# gps_tracker_A2235h.net
KiCad netlist of a schematic drawn in EAGLE
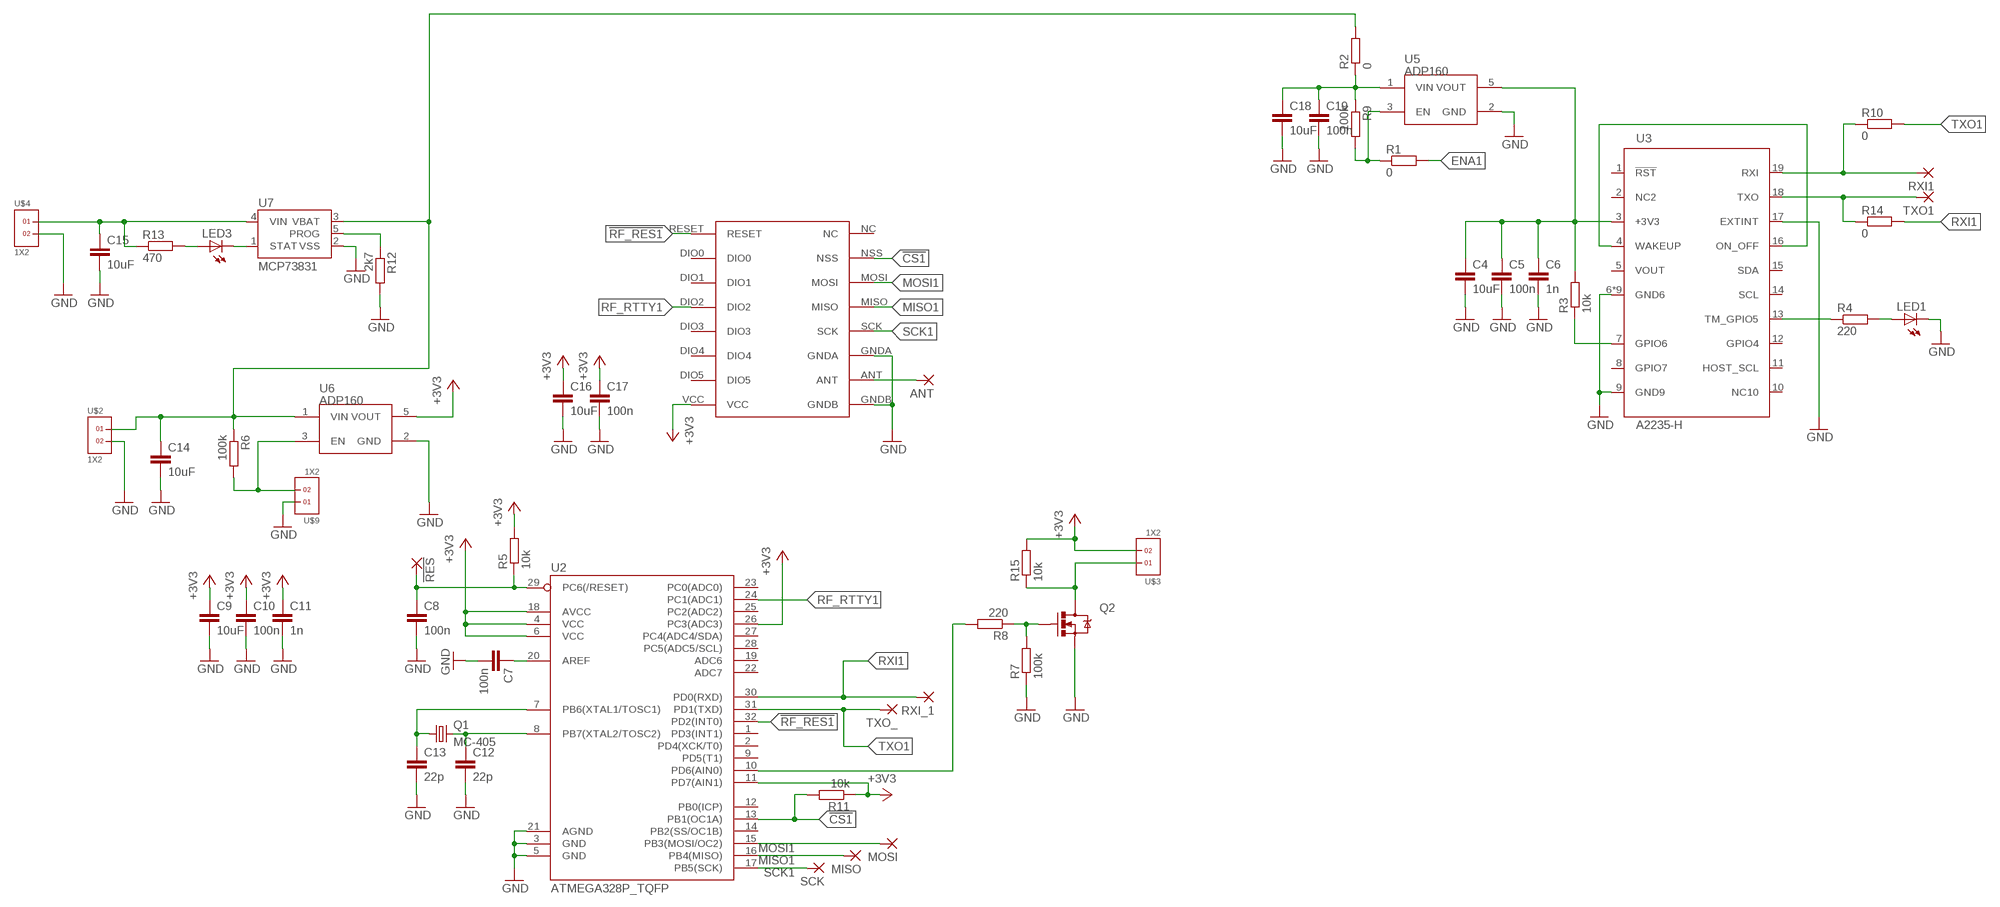
[diagram p0: schematic, sheet 1]

(export (version "E")
  (design (tool "Eeschema 10.0.6"))
  (components
    (comp (ref "!RES")
      (value "SMD2")
      (footprint "eagle-import:SMD1,27-2,54")
      (libsource (lib "eagle-import") (part "SMD2"))
    )
    (comp (ref "ANT")
      (value "SMD2")
      (footprint "eagle-import:SMD1,27-2,54")
      (libsource (lib "eagle-import") (part "SMD2"))
    )
    (comp (ref "C4")
      (value "10uF")
      (footprint "eagle-import:C0603")
      (libsource (lib "eagle-import") (part "C-EUC0603"))
    )
    (comp (ref "C5")
      (value "100n")
      (footprint "eagle-import:C0603")
      (libsource (lib "eagle-import") (part "C-EUC0603"))
    )
    (comp (ref "C6")
      (value "1n")
      (footprint "eagle-import:C0603")
      (libsource (lib "eagle-import") (part "C-EUC0603"))
    )
    (comp (ref "C7")
      (value "100n")
      (footprint "eagle-import:C0603")
      (libsource (lib "eagle-import") (part "C-EUC0603"))
    )
    (comp (ref "C8")
      (value "100n")
      (footprint "eagle-import:C0603")
      (libsource (lib "eagle-import") (part "C-EUC0603"))
    )
    (comp (ref "C9")
      (value "10uF")
      (footprint "eagle-import:C0603")
      (libsource (lib "eagle-import") (part "C-EUC0603"))
    )
    (comp (ref "C10")
      (value "100n")
      (footprint "eagle-import:C0603")
      (libsource (lib "eagle-import") (part "C-EUC0603"))
    )
    (comp (ref "C11")
      (value "1n")
      (footprint "eagle-import:C0603")
      (libsource (lib "eagle-import") (part "C-EUC0603"))
    )
    (comp (ref "C12")
      (value "22p")
      (footprint "eagle-import:C0603")
      (libsource (lib "eagle-import") (part "C-EUC0603"))
    )
    (comp (ref "C13")
      (value "22p")
      (footprint "eagle-import:C0603")
      (libsource (lib "eagle-import") (part "C-EUC0603"))
    )
    (comp (ref "C14")
      (value "10uF")
      (footprint "eagle-import:C0603")
      (libsource (lib "eagle-import") (part "C-EUC0603"))
    )
    (comp (ref "C15")
      (value "10uF")
      (footprint "eagle-import:C0603")
      (libsource (lib "eagle-import") (part "C-EUC0603"))
    )
    (comp (ref "C16")
      (value "10uF")
      (footprint "eagle-import:C0603")
      (libsource (lib "eagle-import") (part "C-EUC0603"))
    )
    (comp (ref "C17")
      (value "100n")
      (footprint "eagle-import:C0603")
      (libsource (lib "eagle-import") (part "C-EUC0603"))
    )
    (comp (ref "C18")
      (value "10uF")
      (footprint "eagle-import:C0603")
      (libsource (lib "eagle-import") (part "C-EUC0603"))
    )
    (comp (ref "C19")
      (value "100n")
      (footprint "eagle-import:C0603")
      (libsource (lib "eagle-import") (part "C-EUC0603"))
    )
    (comp (ref "LED1")
      (value "LEDCHIPLED_0603")
      (footprint "eagle-import:CHIPLED_0603")
      (libsource (lib "eagle-import") (part "LEDCHIPLED_0603"))
    )
    (comp (ref "LED3")
      (value "LEDCHIPLED_0603")
      (footprint "eagle-import:CHIPLED_0603")
      (libsource (lib "eagle-import") (part "LEDCHIPLED_0603"))
    )
    (comp (ref "MISO")
      (value "SMD2")
      (footprint "eagle-import:SMD1,27-2,54")
      (libsource (lib "eagle-import") (part "SMD2"))
    )
    (comp (ref "MOSI")
      (value "SMD2")
      (footprint "eagle-import:SMD1,27-2,54")
      (libsource (lib "eagle-import") (part "SMD2"))
    )
    (comp (ref "Q1")
      (value "MC-405")
      (footprint "eagle-import:MC-405")
      (libsource (lib "eagle-import") (part "MC-405"))
    )
    (comp (ref "Q2")
      (value "MOSFET-NCHANNELAO3404A")
      (footprint "eagle-import:SOT23-3")
      (libsource (lib "eagle-import") (part "MOSFET-NCHANNELAO3404A"))
    )
    (comp (ref "R1")
      (value "0")
      (footprint "eagle-import:R0603")
      (libsource (lib "eagle-import") (part "R-EU_R0603"))
    )
    (comp (ref "R2")
      (value "0")
      (footprint "eagle-import:R0603")
      (libsource (lib "eagle-import") (part "R-EU_R0603"))
    )
    (comp (ref "R3")
      (value "10k")
      (footprint "eagle-import:R0603")
      (libsource (lib "eagle-import") (part "R-EU_R0603"))
    )
    (comp (ref "R4")
      (value "220")
      (footprint "eagle-import:R0603")
      (libsource (lib "eagle-import") (part "R-EU_R0603"))
    )
    (comp (ref "R5")
      (value "10k")
      (footprint "eagle-import:R0603")
      (libsource (lib "eagle-import") (part "R-EU_R0603"))
    )
    (comp (ref "R6")
      (value "100k")
      (footprint "eagle-import:R0603")
      (libsource (lib "eagle-import") (part "R-EU_R0603"))
    )
    (comp (ref "R7")
      (value "100k")
      (footprint "eagle-import:R0603")
      (libsource (lib "eagle-import") (part "R-EU_R0603"))
    )
    (comp (ref "R8")
      (value "220")
      (footprint "eagle-import:R0603")
      (libsource (lib "eagle-import") (part "R-EU_R0603"))
    )
    (comp (ref "R9")
      (value "100k")
      (footprint "eagle-import:R0603")
      (libsource (lib "eagle-import") (part "R-EU_R0603"))
    )
    (comp (ref "R10")
      (value "0")
      (footprint "eagle-import:R0603")
      (libsource (lib "eagle-import") (part "R-EU_R0603"))
    )
    (comp (ref "R11")
      (value "10k")
      (footprint "eagle-import:R0603")
      (libsource (lib "eagle-import") (part "R-EU_R0603"))
    )
    (comp (ref "R12")
      (value "2k7")
      (footprint "eagle-import:R0603")
      (libsource (lib "eagle-import") (part "R-EU_R0603"))
    )
    (comp (ref "R13")
      (value "470")
      (footprint "eagle-import:R0603")
      (libsource (lib "eagle-import") (part "R-EU_R0603"))
    )
    (comp (ref "R14")
      (value "0")
      (footprint "eagle-import:R0603")
      (libsource (lib "eagle-import") (part "R-EU_R0603"))
    )
    (comp (ref "R15")
      (value "10k")
      (footprint "eagle-import:R0603")
      (libsource (lib "eagle-import") (part "R-EU_R0603"))
    )
    (comp (ref "RXI1")
      (value "SMD2")
      (footprint "eagle-import:SMD1,27-2,54")
      (libsource (lib "eagle-import") (part "SMD2"))
    )
    (comp (ref "RXI_1")
      (value "SMD2")
      (footprint "eagle-import:SMD1,27-2,54")
      (libsource (lib "eagle-import") (part "SMD2"))
    )
    (comp (ref "SCK")
      (value "SMD2")
      (footprint "eagle-import:SMD1,27-2,54")
      (libsource (lib "eagle-import") (part "SMD2"))
    )
    (comp (ref "TXO1")
      (value "SMD2")
      (footprint "eagle-import:SMD1,27-2,54")
      (libsource (lib "eagle-import") (part "SMD2"))
    )
    (comp (ref "TXO_")
      (value "SMD2")
      (footprint "eagle-import:SMD1,27-2,54")
      (libsource (lib "eagle-import") (part "SMD2"))
    )
    (comp (ref "U$2")
      (value "1X2")
      (footprint "eagle-import:1X2")
      (libsource (lib "eagle-import") (part "1X2"))
    )
    (comp (ref "U$3")
      (value "1X2")
      (footprint "eagle-import:1X2")
      (libsource (lib "eagle-import") (part "1X2"))
    )
    (comp (ref "U$4")
      (value "1X2")
      (footprint "eagle-import:1X2")
      (libsource (lib "eagle-import") (part "1X2"))
    )
    (comp (ref "U$5")
      (value "RFM69HW")
      (footprint "eagle-import:RFM")
      (libsource (lib "eagle-import") (part "RFM69HW"))
    )
    (comp (ref "U$9")
      (value "1X2")
      (footprint "eagle-import:1X2")
      (libsource (lib "eagle-import") (part "1X2"))
    )
    (comp (ref "U2")
      (value "ATMEGA328P_TQFP")
      (footprint "eagle-import:TQFP32-08")
      (libsource (lib "eagle-import") (part "ATMEGA328P_TQFP"))
    )
    (comp (ref "U3")
      (value "A2235-H")
      (footprint "eagle-import:A2235-H")
      (libsource (lib "eagle-import") (part "A2235-H"))
    )
    (comp (ref "U5")
      (value "ADP160")
      (footprint "eagle-import:SOT23-5")
      (libsource (lib "eagle-import") (part "ADP160"))
    )
    (comp (ref "U6")
      (value "ADP160")
      (footprint "eagle-import:SOT23-5")
      (libsource (lib "eagle-import") (part "ADP160"))
    )
    (comp (ref "U7")
      (value "MCP73831")
      (footprint "eagle-import:SOT23-5")
      (libsource (lib "eagle-import") (part "MCP73831"))
    )
  )
  (nets
    (net (code "1") (name "+3V3") (class "Default")
      (node (ref "C10") (pin "1") (pinfunction "1_1") (pintype "passive"))
      (node (ref "C11") (pin "1") (pinfunction "1_1") (pintype "passive"))
      (node (ref "C16") (pin "1") (pinfunction "1_1") (pintype "passive"))
      (node (ref "C17") (pin "1") (pinfunction "1_1") (pintype "passive"))
      (node (ref "C9") (pin "1") (pinfunction "1_1") (pintype "passive"))
      (node (ref "R11") (pin "1") (pinfunction "1_1") (pintype "passive"))
      (node (ref "R15") (pin "2") (pinfunction "2_2") (pintype "passive"))
      (node (ref "R5") (pin "2") (pinfunction "2_2") (pintype "passive"))
      (node (ref "U$3") (pin "2") (pinfunction "2_2") (pintype "bidirectional"))
      (node (ref "U$5") (pin "VCC") (pinfunction "VCC_VCC") (pintype "bidirectional"))
      (node (ref "U2") (pin "11") (pinfunction "PD7(AIN1)_11") (pintype "bidirectional"))
      (node (ref "U2") (pin "18") (pinfunction "AVCC_18") (pintype "bidirectional"))
      (node (ref "U2") (pin "26") (pinfunction "PC3(ADC3)_26") (pintype "bidirectional"))
      (node (ref "U2") (pin "4") (pinfunction "VCC_4") (pintype "bidirectional"))
      (node (ref "U2") (pin "6") (pinfunction "VCC_6") (pintype "bidirectional"))
      (node (ref "U6") (pin "5") (pinfunction "VOUT_5") (pintype "bidirectional"))
    )
    (net (code "2") (name "/VOUT") (class "Default")
      (node (ref "U3") (pin "5") (pinfunction "VOUT_5") (pintype "power_in"))
    )
    (net (code "3") (name "/~{CS1}") (class "Default")
      (node (ref "R11") (pin "2") (pinfunction "2_2") (pintype "passive"))
      (node (ref "U$5") (pin "NSS") (pinfunction "NSS_NSS") (pintype "bidirectional"))
      (node (ref "U2") (pin "13") (pinfunction "PB1(OC1A)_13") (pintype "bidirectional"))
    )
    (net (code "4") (name "/~{RF_RES1}") (class "Default")
      (node (ref "U$5") (pin "RESET") (pinfunction "RESET_RESET") (pintype "bidirectional"))
      (node (ref "U2") (pin "32") (pinfunction "PD2(INT0)_32") (pintype "bidirectional"))
    )
    (net (code "5") (name "ENA1") (class "Default")
      (node (ref "R1") (pin "2") (pinfunction "2_2") (pintype "passive"))
      (node (ref "R6") (pin "2") (pinfunction "2_2") (pintype "passive"))
      (node (ref "U$9") (pin "2") (pinfunction "2_2") (pintype "bidirectional"))
      (node (ref "U6") (pin "3") (pinfunction "EN_3") (pintype "bidirectional"))
    )
    (net (code "6") (name "GND") (class "Default")
      (node (ref "C10") (pin "2") (pinfunction "2_2") (pintype "passive"))
      (node (ref "C11") (pin "2") (pinfunction "2_2") (pintype "passive"))
      (node (ref "C12") (pin "2") (pinfunction "2_2") (pintype "passive"))
      (node (ref "C13") (pin "2") (pinfunction "2_2") (pintype "passive"))
      (node (ref "C14") (pin "2") (pinfunction "2_2") (pintype "passive"))
      (node (ref "C15") (pin "2") (pinfunction "2_2") (pintype "passive"))
      (node (ref "C16") (pin "2") (pinfunction "2_2") (pintype "passive"))
      (node (ref "C17") (pin "2") (pinfunction "2_2") (pintype "passive"))
      (node (ref "C18") (pin "2") (pinfunction "2_2") (pintype "passive"))
      (node (ref "C19") (pin "2") (pinfunction "2_2") (pintype "passive"))
      (node (ref "C4") (pin "2") (pinfunction "2_2") (pintype "passive"))
      (node (ref "C5") (pin "2") (pinfunction "2_2") (pintype "passive"))
      (node (ref "C6") (pin "2") (pinfunction "2_2") (pintype "passive"))
      (node (ref "C7") (pin "2") (pinfunction "2_2") (pintype "passive"))
      (node (ref "C8") (pin "2") (pinfunction "2_2") (pintype "passive"))
      (node (ref "C9") (pin "2") (pinfunction "2_2") (pintype "passive"))
      (node (ref "LED1") (pin "C") (pinfunction "C_C") (pintype "passive"))
      (node (ref "Q2") (pin "2") (pinfunction "S_2") (pintype "passive"))
      (node (ref "R12") (pin "2") (pinfunction "2_2") (pintype "passive"))
      (node (ref "R7") (pin "1") (pinfunction "1_1") (pintype "passive"))
      (node (ref "U$2") (pin "2") (pinfunction "2_2") (pintype "bidirectional"))
      (node (ref "U$4") (pin "2") (pinfunction "2_2") (pintype "bidirectional"))
      (node (ref "U$5") (pin "GNDA") (pinfunction "GNDA_GNDA") (pintype "bidirectional"))
      (node (ref "U$5") (pin "GNDB") (pinfunction "GNDB_GNDB") (pintype "bidirectional"))
      (node (ref "U$9") (pin "1") (pinfunction "1_1") (pintype "bidirectional"))
      (node (ref "U2") (pin "21") (pinfunction "AGND_21") (pintype "bidirectional"))
      (node (ref "U2") (pin "3") (pinfunction "GND_3") (pintype "bidirectional"))
      (node (ref "U2") (pin "5") (pinfunction "GND_5") (pintype "bidirectional"))
      (node (ref "U3") (pin "101") (pinfunction "GND6_101") (pintype "power_in"))
      (node (ref "U3") (pin "102") (pinfunction "GND6_102") (pintype "power_in"))
      (node (ref "U3") (pin "103") (pinfunction "GND6_103") (pintype "power_in"))
      (node (ref "U3") (pin "104") (pinfunction "GND6_104") (pintype "power_in"))
      (node (ref "U3") (pin "105") (pinfunction "GND6_105") (pintype "power_in"))
      (node (ref "U3") (pin "106") (pinfunction "GND6_106") (pintype "power_in"))
      (node (ref "U3") (pin "107") (pinfunction "GND6_107") (pintype "power_in"))
      (node (ref "U3") (pin "108") (pinfunction "GND6_108") (pintype "power_in"))
      (node (ref "U3") (pin "17") (pinfunction "EXTINT_17") (pintype "input"))
      (node (ref "U3") (pin "6") (pinfunction "GND6_6") (pintype "power_in"))
      (node (ref "U3") (pin "9") (pinfunction "GND9_9") (pintype "power_in"))
      (node (ref "U5") (pin "2") (pinfunction "GND_2") (pintype "bidirectional"))
      (node (ref "U6") (pin "2") (pinfunction "GND_2") (pintype "bidirectional"))
      (node (ref "U7") (pin "2") (pinfunction "VSS_2") (pintype "power_in"))
    )
    (net (code "7") (name "MISO1") (class "Default")
      (node (ref "MISO") (pin "1") (pinfunction "P_1") (pintype "passive"))
      (node (ref "U$5") (pin "MISO") (pinfunction "MISO_MISO") (pintype "bidirectional"))
      (node (ref "U2") (pin "16") (pinfunction "PB4(MISO)_16") (pintype "bidirectional"))
    )
    (net (code "8") (name "MOSI1") (class "Default")
      (node (ref "MOSI") (pin "1") (pinfunction "P_1") (pintype "passive"))
      (node (ref "U$5") (pin "MOSI") (pinfunction "MOSI_MOSI") (pintype "bidirectional"))
      (node (ref "U2") (pin "15") (pinfunction "PB3(MOSI/OC2)_15") (pintype "bidirectional"))
    )
    (net (code "9") (name "Net-(!RES-P)") (class "Default")
      (node (ref "!RES") (pin "1") (pinfunction "P_1") (pintype "passive"))
      (node (ref "C8") (pin "1") (pinfunction "1_1") (pintype "passive"))
      (node (ref "R5") (pin "1") (pinfunction "1_1") (pintype "passive"))
      (node (ref "U2") (pin "29") (pinfunction "PC6(/RESET)_29") (pintype "bidirectional"))
    )
    (net (code "10") (name "Net-(ANT-P)") (class "Default")
      (node (ref "ANT") (pin "1") (pinfunction "P_1") (pintype "passive"))
      (node (ref "U$5") (pin "ANT") (pinfunction "ANT_ANT") (pintype "bidirectional"))
    )
    (net (code "11") (name "Net-(LED1-PadA)") (class "Default")
      (node (ref "LED1") (pin "A") (pinfunction "A_A") (pintype "passive"))
      (node (ref "R4") (pin "2") (pinfunction "2_2") (pintype "passive"))
    )
    (net (code "12") (name "Net-(LED3-PadA)") (class "Default")
      (node (ref "LED3") (pin "A") (pinfunction "A_A") (pintype "passive"))
      (node (ref "R13") (pin "2") (pinfunction "2_2") (pintype "passive"))
    )
    (net (code "13") (name "Net-(Q2-D)") (class "Default")
      (node (ref "Q2") (pin "3") (pinfunction "D_3") (pintype "passive"))
      (node (ref "R15") (pin "1") (pinfunction "1_1") (pintype "passive"))
      (node (ref "U$3") (pin "1") (pinfunction "1_1") (pintype "bidirectional"))
    )
    (net (code "14") (name "Net-(Q2-G)") (class "Default")
      (node (ref "Q2") (pin "1") (pinfunction "G_1") (pintype "passive"))
      (node (ref "R7") (pin "2") (pinfunction "2_2") (pintype "passive"))
      (node (ref "R8") (pin "1") (pinfunction "1_1") (pintype "passive"))
    )
    (net (code "15") (name "Net-(RXI1-P)") (class "Default")
      (node (ref "R10") (pin "1") (pinfunction "1_1") (pintype "passive"))
      (node (ref "RXI1") (pin "1") (pinfunction "P_1") (pintype "passive"))
      (node (ref "U3") (pin "19") (pinfunction "RXI_19") (pintype "input"))
    )
    (net (code "16") (name "Net-(TXO1-P)") (class "Default")
      (node (ref "R14") (pin "1") (pinfunction "1_1") (pintype "passive"))
      (node (ref "TXO1") (pin "1") (pinfunction "P_1") (pintype "passive"))
      (node (ref "U3") (pin "18") (pinfunction "TXO_18") (pintype "output"))
    )
    (net (code "17") (name "Net-(U2-AREF)") (class "Default")
      (node (ref "C7") (pin "1") (pinfunction "1_1") (pintype "passive"))
      (node (ref "U2") (pin "20") (pinfunction "AREF_20") (pintype "bidirectional"))
    )
    (net (code "18") (name "Net-(U2-PB6(XTAL1{slash}TOSC1))") (class "Default")
      (node (ref "C13") (pin "1") (pinfunction "1_1") (pintype "passive"))
      (node (ref "Q1") (pin "1") (pinfunction "1_1") (pintype "passive"))
      (node (ref "U2") (pin "7") (pinfunction "PB6(XTAL1/TOSC1)_7") (pintype "bidirectional"))
    )
    (net (code "19") (name "Net-(U2-PB7(XTAL2{slash}TOSC2))") (class "Default")
      (node (ref "C12") (pin "1") (pinfunction "1_1") (pintype "passive"))
      (node (ref "Q1") (pin "2") (pinfunction "2_2") (pintype "passive"))
      (node (ref "U2") (pin "8") (pinfunction "PB7(XTAL2/TOSC2)_8") (pintype "bidirectional"))
    )
    (net (code "20") (name "Net-(U2-PD6(AIN0))") (class "Default")
      (node (ref "R8") (pin "2") (pinfunction "2_2") (pintype "passive"))
      (node (ref "U2") (pin "10") (pinfunction "PD6(AIN0)_10") (pintype "bidirectional"))
    )
    (net (code "21") (name "Net-(U3-+3V3)") (class "Default")
      (node (ref "C4") (pin "1") (pinfunction "1_1") (pintype "passive"))
      (node (ref "C5") (pin "1") (pinfunction "1_1") (pintype "passive"))
      (node (ref "C6") (pin "1") (pinfunction "1_1") (pintype "passive"))
      (node (ref "R3") (pin "2") (pinfunction "2_2") (pintype "passive"))
      (node (ref "U3") (pin "3") (pinfunction "+3V3_3") (pintype "power_in"))
      (node (ref "U5") (pin "5") (pinfunction "VOUT_5") (pintype "bidirectional"))
    )
    (net (code "22") (name "Net-(U3-GPIO6)") (class "Default")
      (node (ref "R3") (pin "1") (pinfunction "1_1") (pintype "passive"))
      (node (ref "U3") (pin "7") (pinfunction "GPIO6_7") (pintype "input"))
    )
    (net (code "23") (name "Net-(U3-ON_OFF)") (class "Default")
      (node (ref "U3") (pin "16") (pinfunction "ON_OFF_16") (pintype "input"))
      (node (ref "U3") (pin "4") (pinfunction "WAKEUP_4") (pintype "output"))
    )
    (net (code "24") (name "Net-(U3-TM_GPIO5)") (class "Default")
      (node (ref "R4") (pin "1") (pinfunction "1_1") (pintype "passive"))
      (node (ref "U3") (pin "13") (pinfunction "TM_GPIO5_13") (pintype "output"))
    )
    (net (code "25") (name "Net-(U5-EN)") (class "Default")
      (node (ref "R1") (pin "1") (pinfunction "1_1") (pintype "passive"))
      (node (ref "R9") (pin "2") (pinfunction "2_2") (pintype "passive"))
      (node (ref "U5") (pin "3") (pinfunction "EN_3") (pintype "bidirectional"))
    )
    (net (code "26") (name "Net-(U5-VIN)") (class "Default")
      (node (ref "C18") (pin "1") (pinfunction "1_1") (pintype "passive"))
      (node (ref "C19") (pin "1") (pinfunction "1_1") (pintype "passive"))
      (node (ref "R2") (pin "1") (pinfunction "1_1") (pintype "passive"))
      (node (ref "R9") (pin "1") (pinfunction "1_1") (pintype "passive"))
      (node (ref "U5") (pin "1") (pinfunction "VIN_1") (pintype "bidirectional"))
    )
    (net (code "27") (name "Net-(U6-VIN)") (class "Default")
      (node (ref "C14") (pin "1") (pinfunction "1_1") (pintype "passive"))
      (node (ref "R2") (pin "2") (pinfunction "2_2") (pintype "passive"))
      (node (ref "R6") (pin "1") (pinfunction "1_1") (pintype "passive"))
      (node (ref "U$2") (pin "1") (pinfunction "1_1") (pintype "bidirectional"))
      (node (ref "U6") (pin "1") (pinfunction "VIN_1") (pintype "bidirectional"))
      (node (ref "U7") (pin "3") (pinfunction "VBAT_3") (pintype "power_in"))
    )
    (net (code "28") (name "Net-(U7-PROG)") (class "Default")
      (node (ref "R12") (pin "1") (pinfunction "1_1") (pintype "passive"))
      (node (ref "U7") (pin "5") (pinfunction "PROG_5") (pintype "input"))
    )
    (net (code "29") (name "Net-(U7-STAT)") (class "Default")
      (node (ref "LED3") (pin "C") (pinfunction "C_C") (pintype "passive"))
      (node (ref "U7") (pin "1") (pinfunction "STAT_1") (pintype "output"))
    )
    (net (code "30") (name "Net-(U7-VIN)") (class "Default")
      (node (ref "C15") (pin "1") (pinfunction "1_1") (pintype "passive"))
      (node (ref "R13") (pin "1") (pinfunction "1_1") (pintype "passive"))
      (node (ref "U$4") (pin "1") (pinfunction "1_1") (pintype "bidirectional"))
      (node (ref "U7") (pin "4") (pinfunction "VIN_4") (pintype "power_in"))
    )
    (net (code "31") (name "RF_RTTY1") (class "Default")
      (node (ref "U$5") (pin "DIO2") (pinfunction "DIO2_DIO2") (pintype "bidirectional"))
      (node (ref "U2") (pin "24") (pinfunction "PC1(ADC1)_24") (pintype "bidirectional"))
    )
    (net (code "32") (name "RXI1") (class "Default")
      (node (ref "R14") (pin "2") (pinfunction "2_2") (pintype "passive"))
      (node (ref "RXI_1") (pin "1") (pinfunction "P_1") (pintype "passive"))
      (node (ref "U2") (pin "30") (pinfunction "PD0(RXD)_30") (pintype "bidirectional"))
    )
    (net (code "33") (name "SCK1") (class "Default")
      (node (ref "SCK") (pin "1") (pinfunction "P_1") (pintype "passive"))
      (node (ref "U$5") (pin "SCK") (pinfunction "SCK_SCK") (pintype "bidirectional"))
      (node (ref "U2") (pin "17") (pinfunction "PB5(SCK)_17") (pintype "bidirectional"))
    )
    (net (code "34") (name "TXO1") (class "Default")
      (node (ref "R10") (pin "2") (pinfunction "2_2") (pintype "passive"))
      (node (ref "TXO_") (pin "1") (pinfunction "P_1") (pintype "passive"))
      (node (ref "U2") (pin "31") (pinfunction "PD1(TXD)_31") (pintype "bidirectional"))
    )
    (net (code "35") (name "unconnected-(U$5-PadDIO0)") (class "Default")
      (node (ref "U$5") (pin "DIO0") (pinfunction "DIO0_DIO0") (pintype "bidirectional"))
    )
    (net (code "36") (name "unconnected-(U$5-PadDIO1)") (class "Default")
      (node (ref "U$5") (pin "DIO1") (pinfunction "DIO1_DIO1") (pintype "bidirectional"))
    )
    (net (code "37") (name "unconnected-(U$5-PadDIO3)") (class "Default")
      (node (ref "U$5") (pin "DIO3") (pinfunction "DIO3_DIO3") (pintype "bidirectional"))
    )
    (net (code "38") (name "unconnected-(U$5-PadDIO4)") (class "Default")
      (node (ref "U$5") (pin "DIO4") (pinfunction "DIO4_DIO4") (pintype "bidirectional"))
    )
    (net (code "39") (name "unconnected-(U$5-PadDIO5)") (class "Default")
      (node (ref "U$5") (pin "DIO5") (pinfunction "DIO5_DIO5") (pintype "bidirectional"))
    )
    (net (code "40") (name "unconnected-(U$5-PadNC)") (class "Default")
      (node (ref "U$5") (pin "NC") (pinfunction "NC_NC") (pintype "bidirectional"))
    )
    (net (code "41") (name "unconnected-(U2-ADC6-Pad19)") (class "Default")
      (node (ref "U2") (pin "19") (pinfunction "ADC6_19") (pintype "bidirectional"))
    )
    (net (code "42") (name "unconnected-(U2-ADC7-Pad22)") (class "Default")
      (node (ref "U2") (pin "22") (pinfunction "ADC7_22") (pintype "bidirectional"))
    )
    (net (code "43") (name "unconnected-(U2-PB0(ICP)-Pad12)") (class "Default")
      (node (ref "U2") (pin "12") (pinfunction "PB0(ICP)_12") (pintype "bidirectional"))
    )
    (net (code "44") (name "unconnected-(U2-PB2(SS{slash}OC1B)-Pad14)") (class "Default")
      (node (ref "U2") (pin "14") (pinfunction "PB2(SS/OC1B)_14") (pintype "bidirectional"))
    )
    (net (code "45") (name "unconnected-(U2-PC0(ADC0)-Pad23)") (class "Default")
      (node (ref "U2") (pin "23") (pinfunction "PC0(ADC0)_23") (pintype "bidirectional"))
    )
    (net (code "46") (name "unconnected-(U2-PC2(ADC2)-Pad25)") (class "Default")
      (node (ref "U2") (pin "25") (pinfunction "PC2(ADC2)_25") (pintype "bidirectional"))
    )
    (net (code "47") (name "unconnected-(U2-PC4(ADC4{slash}SDA)-Pad27)") (class "Default")
      (node (ref "U2") (pin "27") (pinfunction "PC4(ADC4/SDA)_27") (pintype "bidirectional"))
    )
    (net (code "48") (name "unconnected-(U2-PC5(ADC5{slash}SCL)-Pad28)") (class "Default")
      (node (ref "U2") (pin "28") (pinfunction "PC5(ADC5/SCL)_28") (pintype "bidirectional"))
    )
    (net (code "49") (name "unconnected-(U2-PD3(INT1)-Pad1)") (class "Default")
      (node (ref "U2") (pin "1") (pinfunction "PD3(INT1)_1") (pintype "bidirectional"))
    )
    (net (code "50") (name "unconnected-(U2-PD4(XCK{slash}T0)-Pad2)") (class "Default")
      (node (ref "U2") (pin "2") (pinfunction "PD4(XCK/T0)_2") (pintype "bidirectional"))
    )
    (net (code "51") (name "unconnected-(U2-PD5(T1)-Pad9)") (class "Default")
      (node (ref "U2") (pin "9") (pinfunction "PD5(T1)_9") (pintype "bidirectional"))
    )
    (net (code "52") (name "unconnected-(U3-GPIO4-Pad12)") (class "Default")
      (node (ref "U3") (pin "12") (pinfunction "GPIO4_12") (pintype "input"))
    )
    (net (code "53") (name "unconnected-(U3-GPIO7-Pad8)") (class "Default")
      (node (ref "U3") (pin "8") (pinfunction "GPIO7_8") (pintype "input"))
    )
    (net (code "54") (name "unconnected-(U3-HOST_SCL-Pad11)") (class "Default")
      (node (ref "U3") (pin "11") (pinfunction "HOST_SCL_11") (pintype "input"))
    )
    (net (code "55") (name "unconnected-(U3-NC2-Pad2)") (class "Default")
      (node (ref "U3") (pin "2") (pinfunction "NC2_2") (pintype "no_connect"))
    )
    (net (code "56") (name "unconnected-(U3-NC10-Pad10)") (class "Default")
      (node (ref "U3") (pin "10") (pinfunction "NC10_10") (pintype "no_connect"))
    )
    (net (code "57") (name "unconnected-(U3-SCL-Pad14)") (class "Default")
      (node (ref "U3") (pin "14") (pinfunction "SCL_14") (pintype "input"))
    )
    (net (code "58") (name "unconnected-(U3-SDA-Pad15)") (class "Default")
      (node (ref "U3") (pin "15") (pinfunction "SDA_15") (pintype "bidirectional"))
    )
    (net (code "59") (name "unconnected-(U3-~{RST}-Pad1)") (class "Default")
      (node (ref "U3") (pin "1") (pinfunction "~{RST}_1") (pintype "input"))
    )
  )
)
